# MZQ_TS01_20250701.net
KiCad netlist of a schematic drawn in Altium Designer
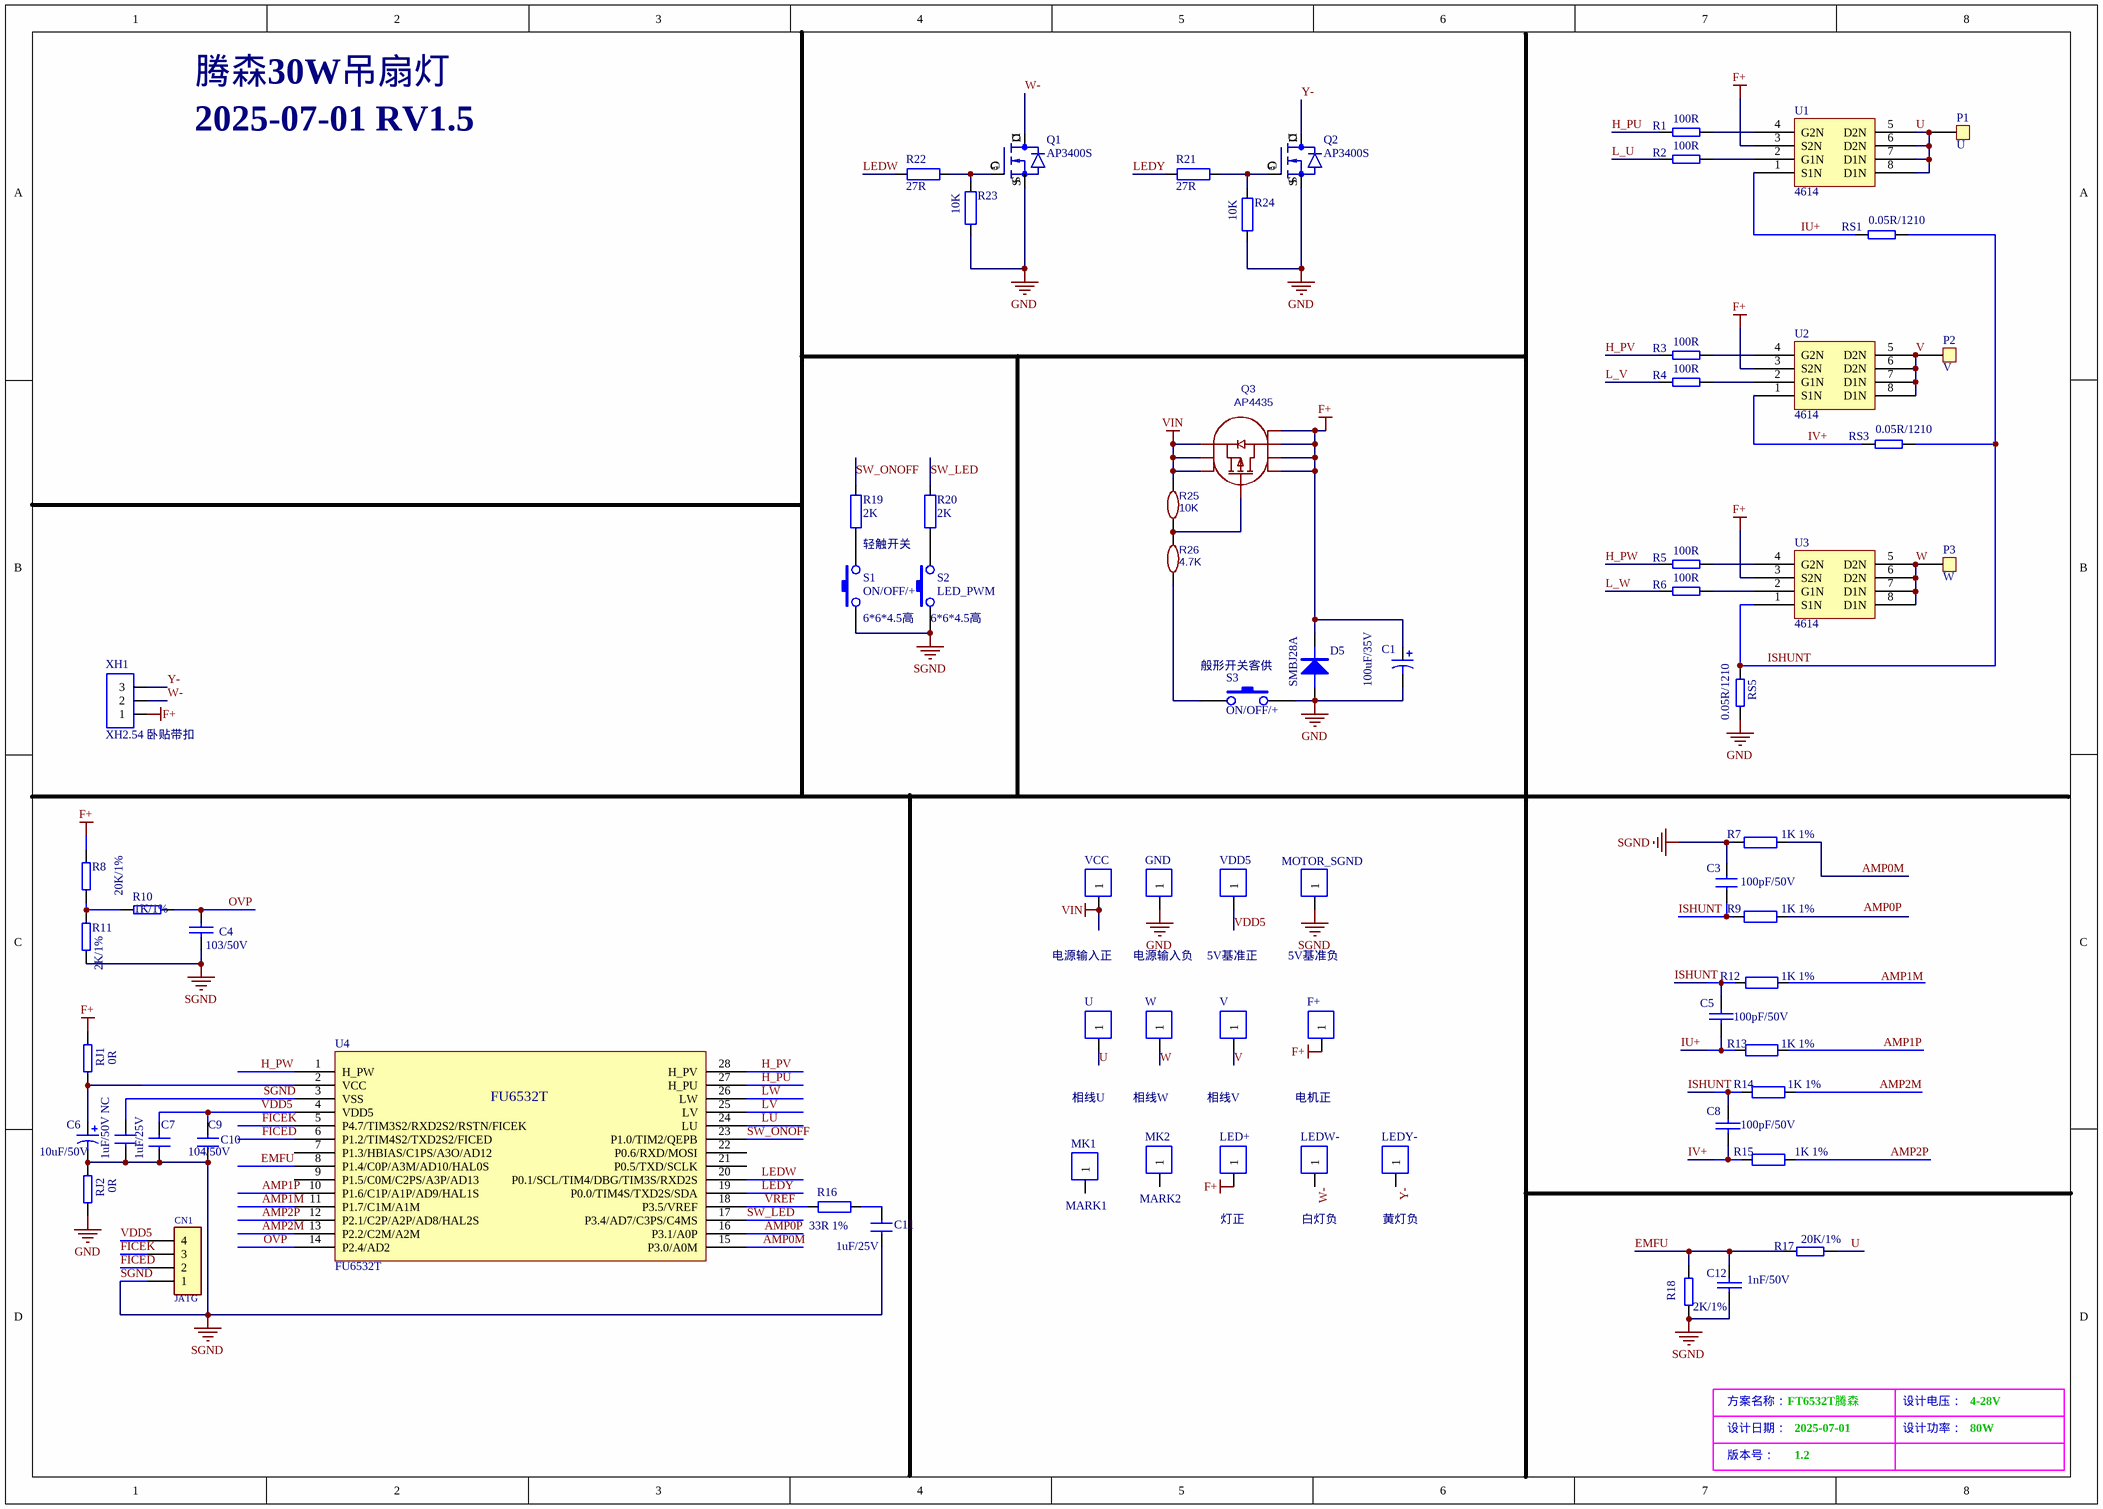
[diagram p0: 腾森_MZQ_TS01_20250701.schdoc]

(export (version "E")
  (design (tool "Eeschema 10.0.6"))
  (components
    (comp (ref "C1")
      (value "100uF/35V")
      (footprint "CAP-6.6X6.6X5.5")
      (description "Polarized Capacitor (Radial)")
      (fields (field (name "PUBLISHER") "Altium Limited"))
      (libsource (lib "*") (part "Cap Pol1"))
    )
    (comp (ref "C3")
      (value "100pF/50V")
      (footprint "0603_C")
      (description "Capacitor")
      (libsource (lib "") (part "CAP_1"))
    )
    (comp (ref "C4")
      (value "103/50V")
      (footprint "0603_C")
      (description "Capacitor")
      (libsource (lib "*") (part "CAP"))
    )
    (comp (ref "C5")
      (value "100pF/50V")
      (footprint "0603_C")
      (description "Capacitor")
      (libsource (lib "*") (part "CAP"))
    )
    (comp (ref "C6")
      (value "10uF/50V")
      (footprint "CAP-6.6X6.6X5.5")
      (description "Polarized Capacitor (Radial)")
      (fields (field (name "PUBLISHER") "Altium Limited"))
      (libsource (lib "*") (part "Cap Pol1"))
    )
    (comp (ref "C7")
      (value "1uF/50V NC")
      (footprint "0603_C")
      (description "Capacitor")
      (libsource (lib "") (part "CAP_1"))
    )
    (comp (ref "C8")
      (value "100pF/50V")
      (footprint "0603_C")
      (description "Capacitor")
      (libsource (lib "*") (part "CAP"))
    )
    (comp (ref "C9")
      (value "1uF/25V")
      (footprint "0603_C")
      (description "Capacitor")
      (libsource (lib "") (part "CAP_1"))
    )
    (comp (ref "C10")
      (value "104/50V")
      (footprint "0603_C")
      (description "Capacitor")
      (libsource (lib "") (part "CAP_1"))
    )
    (comp (ref "C11")
      (value "1uF/25V")
      (footprint "0603_C")
      (description "Capacitor")
      (libsource (lib "") (part "CAP_1"))
    )
    (comp (ref "C12")
      (value "1nF/50V")
      (footprint "0603_C")
      (description "Capacitor")
      (libsource (lib "*") (part "CAP"))
    )
    (comp (ref "CN1")
      (value "JATG")
      (footprint "SMT-烧录口")
      (description "CN")
      (libsource (lib "*") (part "CN4"))
    )
    (comp (ref "D5")
      (value "SMBJ28A")
      (footprint "SMT-SMB(DO-214AA)")
      (description "单向TVS管")
      (libsource (lib "二极管") (part "DIODE"))
    )
    (comp (ref "F+")
      (value "电机正")
      (footprint "test3.0_top")
      (libsource (lib "KENNED 原理图标准封装-2023-9-7") (part "1P"))
    )
    (comp (ref "GND")
      (value "电源输入负")
      (footprint "MI-PAD")
      (libsource (lib "KENNED 原理图标准封装-2023-9-7") (part "1P"))
    )
    (comp (ref "LED+")
      (value "灯正")
      (footprint "MI-PAD")
      (libsource (lib "KENNED 原理图标准封装-2023-9-7") (part "1P"))
    )
    (comp (ref "LEDW-")
      (value "白灯负")
      (footprint "MI-PAD")
      (libsource (lib "KENNED 原理图标准封装-2023-9-7") (part "1P"))
    )
    (comp (ref "LEDY-")
      (value "黄灯负")
      (footprint "MI-PAD")
      (libsource (lib "KENNED 原理图标准封装-2023-9-7") (part "1P"))
    )
    (comp (ref "MK1")
      (value "MARK1")
      (footprint "SMT-MARK")
      (libsource (lib "KENNED 原理图标准封装-2023-9-7") (part "1P"))
    )
    (comp (ref "MK2")
      (value "MARK2")
      (footprint "SMT-MARK")
      (libsource (lib "KENNED 原理图标准封装-2023-9-7") (part "1P"))
    )
    (comp (ref "MOTOR_SGND")
      (value "5V基准负")
      (footprint "test3.0_top")
      (libsource (lib "KENNED 原理图标准封装-2023-9-7") (part "1P"))
    )
    (comp (ref "P1") (value "U") (footprint "MI-PAD") (libsource (lib "SCH") (part "1P")))
    (comp (ref "P2") (value "V") (footprint "MI-PAD") (libsource (lib "SCH") (part "1P")))
    (comp (ref "P3") (value "W") (footprint "MI-PAD") (libsource (lib "") (part "1P_1")))
    (comp (ref "Q1")
      (value "AP3400S")
      (footprint "SMT-SOT-23-MOS管")
      (libsource (lib "KENNED 原理图标准封装-2023-9-7") (part "N MOS"))
    )
    (comp (ref "Q2")
      (value "AP3400S")
      (footprint "SMT-SOT-23-MOS管")
      (libsource (lib "KENNED 原理图标准封装-2023-9-7") (part "N MOS"))
    )
    (comp (ref "Q3")
      (value "AP4435")
      (footprint "SMT-SOP8")
      (fields (field (name "BOM_MANUFACTURER PART") "AO4459") (field (name "BOM_SUPPLIER PART") "C49047"))
      (libsource (lib "altium-import") (part "root_1_AO4459_"))
    )
    (comp (ref "R1") (value "100R") (footprint "0603") (libsource (lib "*") (part "RES2")))
    (comp (ref "R2") (value "100R") (footprint "0603") (libsource (lib "*") (part "RES2")))
    (comp (ref "R3") (value "100R") (footprint "0603") (libsource (lib "*") (part "RES2")))
    (comp (ref "R4") (value "100R") (footprint "0603") (libsource (lib "*") (part "RES2")))
    (comp (ref "R5") (value "100R") (footprint "0603") (libsource (lib "*") (part "RES2")))
    (comp (ref "R6") (value "100R") (footprint "0603") (libsource (lib "*") (part "RES2")))
    (comp (ref "R7") (value "1K 1%") (footprint "0603_R") (libsource (lib "*") (part "Res")))
    (comp (ref "R8") (value "20K/1%") (footprint "0603") (libsource (lib "*") (part "RES2")))
    (comp (ref "R9") (value "1K 1%") (footprint "0603_R") (libsource (lib "*") (part "Res")))
    (comp (ref "R10") (value "1K/1%") (footprint "0603") (libsource (lib "*") (part "RES2")))
    (comp (ref "R11") (value "2K/1%") (footprint "0603") (libsource (lib "*") (part "RES2")))
    (comp (ref "R12") (value "1K 1%") (footprint "0603_R") (libsource (lib "*") (part "Res")))
    (comp (ref "R13") (value "1K 1%") (footprint "0603_R") (libsource (lib "*") (part "Res")))
    (comp (ref "R14") (value "1K 1%") (footprint "0603_R") (libsource (lib "*") (part "Res")))
    (comp (ref "R15") (value "1K 1%") (footprint "0603_R") (libsource (lib "*") (part "Res")))
    (comp (ref "R16") (value "33R 1%") (footprint "0603_R") (libsource (lib "*") (part "Res")))
    (comp (ref "R17") (value "20K/1%") (footprint "0603") (libsource (lib "*") (part "RES2")))
    (comp (ref "R18") (value "2K/1%") (footprint "0603") (libsource (lib "*") (part "RES2")))
    (comp (ref "R19") (value "2K") (footprint "0603_R") (libsource (lib "*") (part "Res")))
    (comp (ref "R20") (value "2K") (footprint "0603_R") (libsource (lib "*") (part "Res")))
    (comp (ref "R21") (value "27R") (footprint "0603_R") (libsource (lib "*") (part "Res")))
    (comp (ref "R22") (value "27R") (footprint "0603_R") (libsource (lib "*") (part "Res")))
    (comp (ref "R23") (value "10K") (footprint "0603_R") (libsource (lib "*") (part "Res")))
    (comp (ref "R24") (value "10K") (footprint "0603_R") (libsource (lib "*") (part "Res")))
    (comp (ref "R25")
      (value "10K")
      (footprint "0603_R")
      (fields
        (field (name "BOM_MANUFACTURER PART") "0402WGJ0165TCE")
        (field (name "BOM_SUPPLIER PART") "C57065")
      )
      (libsource (lib "altium-import") (part "root_1_mirrored_51K_"))
    )
    (comp (ref "R26")
      (value "4.7K")
      (footprint "0603_R")
      (fields
        (field (name "BOM_MANUFACTURER PART") "0402WGJ0165TCE")
        (field (name "BOM_SUPPLIER PART") "C57065")
      )
      (libsource (lib "altium-import") (part "root_1_51K_"))
    )
    (comp (ref "RJ1") (value "0R") (footprint "1206") (libsource (lib "*") (part "RES2")))
    (comp (ref "RJ2") (value "0R") (footprint "0603_R") (libsource (lib "*") (part "RES2")))
    (comp (ref "RS1") (value "0.05R/1210") (footprint "SMT-1210R") (libsource (lib "*") (part "RES2")))
    (comp (ref "RS3") (value "0.05R/1210") (footprint "SMT-1210R") (libsource (lib "*") (part "RES2")))
    (comp (ref "RS5") (value "0.05R/1210") (footprint "SMT-1210R") (libsource (lib "*") (part "RES2")))
    (comp (ref "S1") (value "ON/OFF/+") (footprint "SMT-6X6轻触开关通用") (libsource (lib "*") (part "SW-PB")))
    (comp (ref "S2") (value "LED_PWM") (footprint "SMT-6X6轻触开关通用") (libsource (lib "*") (part "SW-PB")))
    (comp (ref "S3")
      (value "ON/OFF/+")
      (footprint "SW-TH_2P-L15.0-W10.5-P5.00")
      (libsource (lib "*") (part "SW-PB"))
    )
    (comp (ref "U")
      (value "相线U")
      (footprint "test3.0_top")
      (libsource (lib "KENNED 原理图标准封装-2023-9-7") (part "1P"))
    )
    (comp (ref "U1") (value "4614") (footprint "SO-8") (libsource (lib "*") (part "P2804NVG")))
    (comp (ref "U2") (value "4614") (footprint "SO-8") (libsource (lib "*") (part "P2804NVG")))
    (comp (ref "U3") (value "4614") (footprint "SO-8") (libsource (lib "*") (part "P2804NVG")))
    (comp (ref "U4") (value "FU6532T") (footprint "TSSOP28") (libsource (lib "Schlib1") (part "FU6532T")))
    (comp (ref "V")
      (value "相线V")
      (footprint "test3.0_top")
      (libsource (lib "KENNED 原理图标准封装-2023-9-7") (part "1P"))
    )
    (comp (ref "VCC")
      (value "电源输入正")
      (footprint "MI-PAD")
      (libsource (lib "KENNED 原理图标准封装-2023-9-7") (part "1P"))
    )
    (comp (ref "VDD5")
      (value "5V基准正")
      (footprint "test3.0_top")
      (libsource (lib "KENNED 原理图标准封装-2023-9-7") (part "1P"))
    )
    (comp (ref "W")
      (value "相线W")
      (footprint "test3.0_top")
      (libsource (lib "KENNED 原理图标准封装-2023-9-7") (part "1P"))
    )
    (comp (ref "XH1")
      (value "XH2.54 卧贴带扣")
      (footprint "MI-VH3-2.5")
      (libsource (lib "KENNED 原理图标准封装-2023-9-7") (part "3P"))
    )
  )
  (nets
    (net (code "1") (name "/AMP0M") (class "Default")
      (node (ref "R7") (pin "2") (pinfunction "2_2") (pintype "passive"))
      (node (ref "U4") (pin "15") (pinfunction "P3.0/A0M_15") (pintype "passive"))
    )
    (net (code "2") (name "/AMP0P") (class "Default")
      (node (ref "U4") (pin "16") (pinfunction "P3.1/A0P_16") (pintype "passive"))
    )
    (net (code "3") (name "/AMP1M") (class "Default")
      (node (ref "U4") (pin "11") (pinfunction "P1.7/C1M/A1M_11") (pintype "passive"))
    )
    (net (code "4") (name "/AMP1P") (class "Default")
      (node (ref "R13") (pin "2") (pinfunction "2_2") (pintype "passive"))
      (node (ref "U4") (pin "10") (pinfunction "P1.6/C1P/A1P/AD9/HAL1S_10") (pintype "passive"))
    )
    (net (code "5") (name "/AMP2M") (class "Default")
      (node (ref "R14") (pin "2") (pinfunction "2_2") (pintype "passive"))
      (node (ref "U4") (pin "13") (pinfunction "P2.2/C2M/A2M_13") (pintype "passive"))
    )
    (net (code "6") (name "/AMP2P") (class "Default")
      (node (ref "R15") (pin "2") (pinfunction "2_2") (pintype "passive"))
      (node (ref "U4") (pin "12") (pinfunction "P2.1/C2P/A2P/AD8/HAL2S_12") (pintype "passive"))
    )
    (net (code "7") (name "/EMFU") (class "Default")
      (node (ref "C12") (pin "1") (pinfunction "1_1") (pintype "passive"))
      (node (ref "R17") (pin "1") (pinfunction "1_1") (pintype "passive"))
      (node (ref "R18") (pin "1") (pinfunction "1_1") (pintype "passive"))
      (node (ref "U4") (pin "8") (pinfunction "P1.4/C0P/A3M/AD10/HAL0S_8") (pintype "passive"))
    )
    (net (code "8") (name "/FICED") (class "Default")
      (node (ref "CN1") (pin "2") (pinfunction "2_2") (pintype "passive"))
      (node (ref "U4") (pin "6") (pinfunction "P1.2/TIM4S2/TXD2S2/FICED_6") (pintype "passive"))
    )
    (net (code "9") (name "/FICEK") (class "Default")
      (node (ref "CN1") (pin "3") (pinfunction "3_3") (pintype "passive"))
      (node (ref "U4") (pin "5") (pinfunction "P4.7/TIM3S2/RXD2S2/RSTN/FICEK_5") (pintype "passive"))
    )
    (net (code "10") (name "/H_PU") (class "Default")
      (node (ref "R1") (pin "2") (pinfunction "10_2") (pintype "passive"))
      (node (ref "U4") (pin "27") (pinfunction "H_PU_27") (pintype "passive"))
    )
    (net (code "11") (name "/H_PV") (class "Default")
      (node (ref "R3") (pin "2") (pinfunction "10_2") (pintype "passive"))
      (node (ref "U4") (pin "28") (pinfunction "H_PV_28") (pintype "passive"))
    )
    (net (code "12") (name "/H_PW") (class "Default")
      (node (ref "R5") (pin "2") (pinfunction "10_2") (pintype "passive"))
      (node (ref "U4") (pin "1") (pinfunction "H_PW_1") (pintype "passive"))
    )
    (net (code "13") (name "/ISHUNT") (class "Default")
      (node (ref "C3") (pin "2") (pinfunction "2_2") (pintype "passive"))
      (node (ref "C5") (pin "1") (pinfunction "1_1") (pintype "passive"))
      (node (ref "C8") (pin "1") (pinfunction "1_1") (pintype "passive"))
      (node (ref "R12") (pin "1") (pinfunction "1_1") (pintype "passive"))
      (node (ref "R14") (pin "1") (pinfunction "1_1") (pintype "passive"))
      (node (ref "R9") (pin "1") (pinfunction "1_1") (pintype "passive"))
      (node (ref "RS1") (pin "2") (pinfunction "10_2") (pintype "passive"))
      (node (ref "RS3") (pin "2") (pinfunction "10_2") (pintype "passive"))
      (node (ref "RS5") (pin "1") (pinfunction "1_1") (pintype "passive"))
      (node (ref "U3") (pin "1") (pinfunction "S1N_1") (pintype "passive"))
    )
    (net (code "14") (name "/IU+") (class "Default")
      (node (ref "C5") (pin "2") (pinfunction "2_2") (pintype "passive"))
      (node (ref "R13") (pin "1") (pinfunction "1_1") (pintype "passive"))
      (node (ref "RS1") (pin "1") (pinfunction "1_1") (pintype "passive"))
      (node (ref "U1") (pin "1") (pinfunction "S1N_1") (pintype "passive"))
    )
    (net (code "15") (name "/IV+") (class "Default")
      (node (ref "C8") (pin "2") (pinfunction "2_2") (pintype "passive"))
      (node (ref "R15") (pin "1") (pinfunction "1_1") (pintype "passive"))
      (node (ref "RS3") (pin "1") (pinfunction "1_1") (pintype "passive"))
      (node (ref "U2") (pin "1") (pinfunction "S1N_1") (pintype "passive"))
    )
    (net (code "16") (name "/LEDW") (class "Default")
      (node (ref "R22") (pin "1") (pinfunction "1_1") (pintype "passive"))
      (node (ref "U4") (pin "20") (pinfunction "P0.1/SCL/TIM4/DBG/TIM3S/RXD2S_20") (pintype "passive"))
    )
    (net (code "17") (name "/LEDY") (class "Default")
      (node (ref "R21") (pin "1") (pinfunction "1_1") (pintype "passive"))
      (node (ref "U4") (pin "19") (pinfunction "P0.0/TIM4S/TXD2S/SDA_19") (pintype "passive"))
    )
    (net (code "18") (name "/LU") (class "Default")
      (node (ref "U4") (pin "24") (pinfunction "LU_24") (pintype "passive"))
    )
    (net (code "19") (name "/LV") (class "Default")
      (node (ref "U4") (pin "25") (pinfunction "LV_25") (pintype "passive"))
    )
    (net (code "20") (name "/LW") (class "Default")
      (node (ref "U4") (pin "26") (pinfunction "LW_26") (pintype "passive"))
    )
    (net (code "21") (name "/L_U") (class "Default")
      (node (ref "R2") (pin "2") (pinfunction "10_2") (pintype "passive"))
    )
    (net (code "22") (name "/L_V") (class "Default")
      (node (ref "R4") (pin "2") (pinfunction "10_2") (pintype "passive"))
    )
    (net (code "23") (name "/L_W") (class "Default")
      (node (ref "R6") (pin "2") (pinfunction "10_2") (pintype "passive"))
    )
    (net (code "24") (name "/OVP") (class "Default")
      (node (ref "C4") (pin "1") (pinfunction "1_1") (pintype "passive"))
      (node (ref "R10") (pin "1") (pinfunction "1_1") (pintype "passive"))
      (node (ref "U4") (pin "14") (pinfunction "P2.4/AD2_14") (pintype "passive"))
    )
    (net (code "25") (name "/SW_LED") (class "Default")
      (node (ref "R20") (pin "2") (pinfunction "2_2") (pintype "passive"))
      (node (ref "U4") (pin "17") (pinfunction "P3.4/AD7/C3PS/C4MS_17") (pintype "passive"))
    )
    (net (code "26") (name "/SW_ONOFF") (class "Default")
      (node (ref "R19") (pin "2") (pinfunction "2_2") (pintype "passive"))
      (node (ref "U4") (pin "23") (pinfunction "P1.0/TIM2/QEPB_23") (pintype "passive"))
    )
    (net (code "27") (name "/U") (class "Default")
      (node (ref "P1") (pin "1") (pinfunction "1_1") (pintype "passive"))
      (node (ref "R17") (pin "2") (pinfunction "10_2") (pintype "passive"))
      (node (ref "U") (pin "1") (pinfunction "1_1") (pintype "passive"))
      (node (ref "U1") (pin "5") (pinfunction "D2N_5") (pintype "passive"))
      (node (ref "U1") (pin "6") (pinfunction "D2N_6") (pintype "passive"))
      (node (ref "U1") (pin "7") (pinfunction "D1N_7") (pintype "passive"))
      (node (ref "U1") (pin "8") (pinfunction "D1N_8") (pintype "passive"))
    )
    (net (code "28") (name "/V") (class "Default")
      (node (ref "P2") (pin "1") (pinfunction "1_1") (pintype "passive"))
      (node (ref "U2") (pin "5") (pinfunction "D2N_5") (pintype "passive"))
      (node (ref "U2") (pin "6") (pinfunction "D2N_6") (pintype "passive"))
      (node (ref "U2") (pin "7") (pinfunction "D1N_7") (pintype "passive"))
      (node (ref "U2") (pin "8") (pinfunction "D1N_8") (pintype "passive"))
      (node (ref "V") (pin "1") (pinfunction "1_1") (pintype "passive"))
    )
    (net (code "29") (name "/VDD5") (class "Default")
      (node (ref "C10") (pin "1") (pinfunction "1_1") (pintype "passive"))
      (node (ref "C9") (pin "1") (pinfunction "1_1") (pintype "passive"))
      (node (ref "CN1") (pin "4") (pinfunction "4_4") (pintype "passive"))
      (node (ref "U4") (pin "4") (pinfunction "VDD5_4") (pintype "passive"))
      (node (ref "VDD5") (pin "1") (pinfunction "1_1") (pintype "passive"))
    )
    (net (code "30") (name "/VREF") (class "Default")
      (node (ref "R16") (pin "1") (pinfunction "1_1") (pintype "passive"))
      (node (ref "U4") (pin "18") (pinfunction "P3.5/VREF_18") (pintype "passive"))
    )
    (net (code "31") (name "/W") (class "Default")
      (node (ref "P3") (pin "1") (pinfunction "1_1") (pintype "passive"))
      (node (ref "U3") (pin "5") (pinfunction "D2N_5") (pintype "passive"))
      (node (ref "U3") (pin "6") (pinfunction "D2N_6") (pintype "passive"))
      (node (ref "U3") (pin "7") (pinfunction "D1N_7") (pintype "passive"))
      (node (ref "U3") (pin "8") (pinfunction "D1N_8") (pintype "passive"))
      (node (ref "W") (pin "1") (pinfunction "1_1") (pintype "passive"))
    )
    (net (code "32") (name "/W-") (class "Default")
      (node (ref "LEDW-") (pin "1") (pinfunction "1_1") (pintype "passive"))
      (node (ref "Q1") (pin "D") (pinfunction "D_D") (pintype "passive"))
      (node (ref "XH1") (pin "2") (pinfunction "2_2") (pintype "passive"))
    )
    (net (code "33") (name "/Y-") (class "Default")
      (node (ref "LEDY-") (pin "1") (pinfunction "1_1") (pintype "passive"))
      (node (ref "Q2") (pin "D") (pinfunction "D_D") (pintype "passive"))
      (node (ref "XH1") (pin "3") (pinfunction "3_3") (pintype "passive"))
    )
    (net (code "34") (name "F+") (class "Default")
      (node (ref "C1") (pin "1") (pinfunction "1_1") (pintype "passive"))
      (node (ref "D5") (pin "K") (pinfunction "K_K") (pintype "passive"))
      (node (ref "F+") (pin "1") (pinfunction "1_1") (pintype "passive"))
      (node (ref "LED+") (pin "1") (pinfunction "1_1") (pintype "passive"))
      (node (ref "Q3") (pin "5") (pinfunction "D_5") (pintype "passive"))
      (node (ref "Q3") (pin "6") (pinfunction "D_6") (pintype "passive"))
      (node (ref "Q3") (pin "7") (pinfunction "D_7") (pintype "passive"))
      (node (ref "Q3") (pin "8") (pinfunction "D_8") (pintype "passive"))
      (node (ref "R8") (pin "2") (pinfunction "10_2") (pintype "passive"))
      (node (ref "RJ1") (pin "1") (pinfunction "1_1") (pintype "passive"))
      (node (ref "U1") (pin "3") (pinfunction "S2N_3") (pintype "passive"))
      (node (ref "U2") (pin "3") (pinfunction "S2N_3") (pintype "passive"))
      (node (ref "U3") (pin "3") (pinfunction "S2N_3") (pintype "passive"))
      (node (ref "XH1") (pin "1") (pinfunction "1_1") (pintype "passive"))
    )
    (net (code "35") (name "GND") (class "Default")
      (node (ref "C1") (pin "2") (pinfunction "2_2") (pintype "passive"))
      (node (ref "D5") (pin "A") (pinfunction "A_A") (pintype "passive"))
      (node (ref "GND") (pin "1") (pinfunction "1_1") (pintype "passive"))
      (node (ref "Q1") (pin "S") (pinfunction "S_S") (pintype "passive"))
      (node (ref "Q2") (pin "S") (pinfunction "S_S") (pintype "passive"))
      (node (ref "R23") (pin "2") (pinfunction "2_2") (pintype "passive"))
      (node (ref "R24") (pin "2") (pinfunction "2_2") (pintype "passive"))
      (node (ref "RJ2") (pin "2") (pinfunction "10_2") (pintype "passive"))
      (node (ref "RS5") (pin "2") (pinfunction "10_2") (pintype "passive"))
      (node (ref "S3") (pin "1") (pinfunction "1_1") (pintype "passive"))
    )
    (net (code "36") (name "Net-(C11-Pad2)") (class "Default")
      (node (ref "C11") (pin "2") (pinfunction "2_2") (pintype "passive"))
      (node (ref "R16") (pin "2") (pinfunction "2_2") (pintype "passive"))
    )
    (net (code "37") (name "Net-(Q1-PadG)") (class "Default")
      (node (ref "Q1") (pin "G") (pinfunction "G_G") (pintype "passive"))
      (node (ref "R22") (pin "2") (pinfunction "2_2") (pintype "passive"))
      (node (ref "R23") (pin "1") (pinfunction "1_1") (pintype "passive"))
    )
    (net (code "38") (name "Net-(Q2-PadG)") (class "Default")
      (node (ref "Q2") (pin "G") (pinfunction "G_G") (pintype "passive"))
      (node (ref "R21") (pin "2") (pinfunction "2_2") (pintype "passive"))
      (node (ref "R24") (pin "1") (pinfunction "1_1") (pintype "passive"))
    )
    (net (code "39") (name "Net-(Q3-G)") (class "Default")
      (node (ref "Q3") (pin "4") (pinfunction "G_4") (pintype "passive"))
      (node (ref "R25") (pin "1") (pinfunction "1_1") (pintype "passive"))
      (node (ref "R26") (pin "2") (pinfunction "2_2") (pintype "passive"))
    )
    (net (code "40") (name "Net-(R10-10)") (class "Default")
      (node (ref "R10") (pin "2") (pinfunction "10_2") (pintype "passive"))
      (node (ref "R11") (pin "2") (pinfunction "10_2") (pintype "passive"))
      (node (ref "R8") (pin "1") (pinfunction "1_1") (pintype "passive"))
    )
    (net (code "41") (name "Net-(R19-Pad1)") (class "Default")
      (node (ref "R19") (pin "1") (pinfunction "1_1") (pintype "passive"))
      (node (ref "S1") (pin "1") (pinfunction "1_1") (pintype "passive"))
    )
    (net (code "42") (name "Net-(R20-Pad1)") (class "Default")
      (node (ref "R20") (pin "1") (pinfunction "1_1") (pintype "passive"))
      (node (ref "S2") (pin "1") (pinfunction "1_1") (pintype "passive"))
    )
    (net (code "43") (name "Net-(R26-Pad1)") (class "Default")
      (node (ref "R26") (pin "1") (pinfunction "1_1") (pintype "passive"))
      (node (ref "S3") (pin "2") (pinfunction "2_2") (pintype "passive"))
    )
    (net (code "44") (name "Net-(RJ1-10)") (class "Default")
      (node (ref "C6") (pin "1") (pinfunction "1_1") (pintype "passive"))
      (node (ref "RJ1") (pin "2") (pinfunction "10_2") (pintype "passive"))
      (node (ref "U4") (pin "2") (pinfunction "VCC_2") (pintype "passive"))
    )
    (net (code "45") (name "Net-(U1-G1N)") (class "Default")
      (node (ref "R2") (pin "1") (pinfunction "1_1") (pintype "passive"))
      (node (ref "U1") (pin "2") (pinfunction "G1N_2") (pintype "passive"))
    )
    (net (code "46") (name "Net-(U1-G2N)") (class "Default")
      (node (ref "R1") (pin "1") (pinfunction "1_1") (pintype "passive"))
      (node (ref "U1") (pin "4") (pinfunction "G2N_4") (pintype "passive"))
    )
    (net (code "47") (name "Net-(U2-G1N)") (class "Default")
      (node (ref "R4") (pin "1") (pinfunction "1_1") (pintype "passive"))
      (node (ref "U2") (pin "2") (pinfunction "G1N_2") (pintype "passive"))
    )
    (net (code "48") (name "Net-(U2-G2N)") (class "Default")
      (node (ref "R3") (pin "1") (pinfunction "1_1") (pintype "passive"))
      (node (ref "U2") (pin "4") (pinfunction "G2N_4") (pintype "passive"))
    )
    (net (code "49") (name "Net-(U3-G1N)") (class "Default")
      (node (ref "R6") (pin "1") (pinfunction "1_1") (pintype "passive"))
      (node (ref "U3") (pin "2") (pinfunction "G1N_2") (pintype "passive"))
    )
    (net (code "50") (name "Net-(U3-G2N)") (class "Default")
      (node (ref "R5") (pin "1") (pinfunction "1_1") (pintype "passive"))
      (node (ref "U3") (pin "4") (pinfunction "G2N_4") (pintype "passive"))
    )
    (net (code "51") (name "SGND") (class "Default")
      (node (ref "C10") (pin "2") (pinfunction "2_2") (pintype "passive"))
      (node (ref "C11") (pin "1") (pinfunction "1_1") (pintype "passive"))
      (node (ref "C12") (pin "2") (pinfunction "2_2") (pintype "passive"))
      (node (ref "C3") (pin "1") (pinfunction "1_1") (pintype "passive"))
      (node (ref "C4") (pin "2") (pinfunction "2_2") (pintype "passive"))
      (node (ref "C6") (pin "2") (pinfunction "2_2") (pintype "passive"))
      (node (ref "C7") (pin "1") (pinfunction "1_1") (pintype "passive"))
      (node (ref "C7") (pin "2") (pinfunction "2_2") (pintype "passive"))
      (node (ref "C9") (pin "2") (pinfunction "2_2") (pintype "passive"))
      (node (ref "CN1") (pin "1") (pinfunction "1_1") (pintype "passive"))
      (node (ref "MOTOR_SGND") (pin "1") (pinfunction "1_1") (pintype "passive"))
      (node (ref "R11") (pin "1") (pinfunction "1_1") (pintype "passive"))
      (node (ref "R18") (pin "2") (pinfunction "10_2") (pintype "passive"))
      (node (ref "R7") (pin "1") (pinfunction "1_1") (pintype "passive"))
      (node (ref "RJ2") (pin "1") (pinfunction "1_1") (pintype "passive"))
      (node (ref "S1") (pin "2") (pinfunction "2_2") (pintype "passive"))
      (node (ref "S2") (pin "2") (pinfunction "2_2") (pintype "passive"))
      (node (ref "U4") (pin "3") (pinfunction "VSS_3") (pintype "passive"))
    )
    (net (code "52") (name "VIN") (class "Default")
      (node (ref "Q3") (pin "1") (pinfunction "S_1") (pintype "passive"))
      (node (ref "Q3") (pin "2") (pinfunction "S_2") (pintype "passive"))
      (node (ref "Q3") (pin "3") (pinfunction "S_3") (pintype "passive"))
      (node (ref "R25") (pin "2") (pinfunction "2_2") (pintype "passive"))
      (node (ref "VCC") (pin "1") (pinfunction "1_1") (pintype "passive"))
    )
    (net (code "53") (name "unconnected-(MK1-Pad1)") (class "Default")
      (node (ref "MK1") (pin "1") (pinfunction "1_1") (pintype "passive"))
    )
    (net (code "54") (name "unconnected-(MK2-Pad1)") (class "Default")
      (node (ref "MK2") (pin "1") (pinfunction "1_1") (pintype "passive"))
    )
    (net (code "55") (name "unconnected-(R9-Pad2)") (class "Default")
      (node (ref "R9") (pin "2") (pinfunction "2_2") (pintype "passive"))
    )
    (net (code "56") (name "unconnected-(R12-Pad2)") (class "Default")
      (node (ref "R12") (pin "2") (pinfunction "2_2") (pintype "passive"))
    )
    (net (code "57") (name "unconnected-(U4-P0.5{slash}TXD{slash}SCLK-Pad21)") (class "Default")
      (node (ref "U4") (pin "21") (pinfunction "P0.5/TXD/SCLK_21") (pintype "passive"))
    )
    (net (code "58") (name "unconnected-(U4-P0.6{slash}RXD{slash}MOSI-Pad22)") (class "Default")
      (node (ref "U4") (pin "22") (pinfunction "P0.6/RXD/MOSI_22") (pintype "passive"))
    )
    (net (code "59") (name "unconnected-(U4-P1.3{slash}HBIAS{slash}C1PS{slash}A3O{slash}AD12-Pad7)") (class "Default")
      (node (ref "U4") (pin "7") (pinfunction "P1.3/HBIAS/C1PS/A3O/AD12_7") (pintype "passive"))
    )
    (net (code "60") (name "unconnected-(U4-P1.5{slash}C0M{slash}C2PS{slash}A3P{slash}AD13-Pad9)") (class "Default")
      (node (ref "U4") (pin "9") (pinfunction "P1.5/C0M/C2PS/A3P/AD13_9") (pintype "passive"))
    )
  )
)
